# PWR.net
KiCad netlist of a schematic drawn in Altium Designer
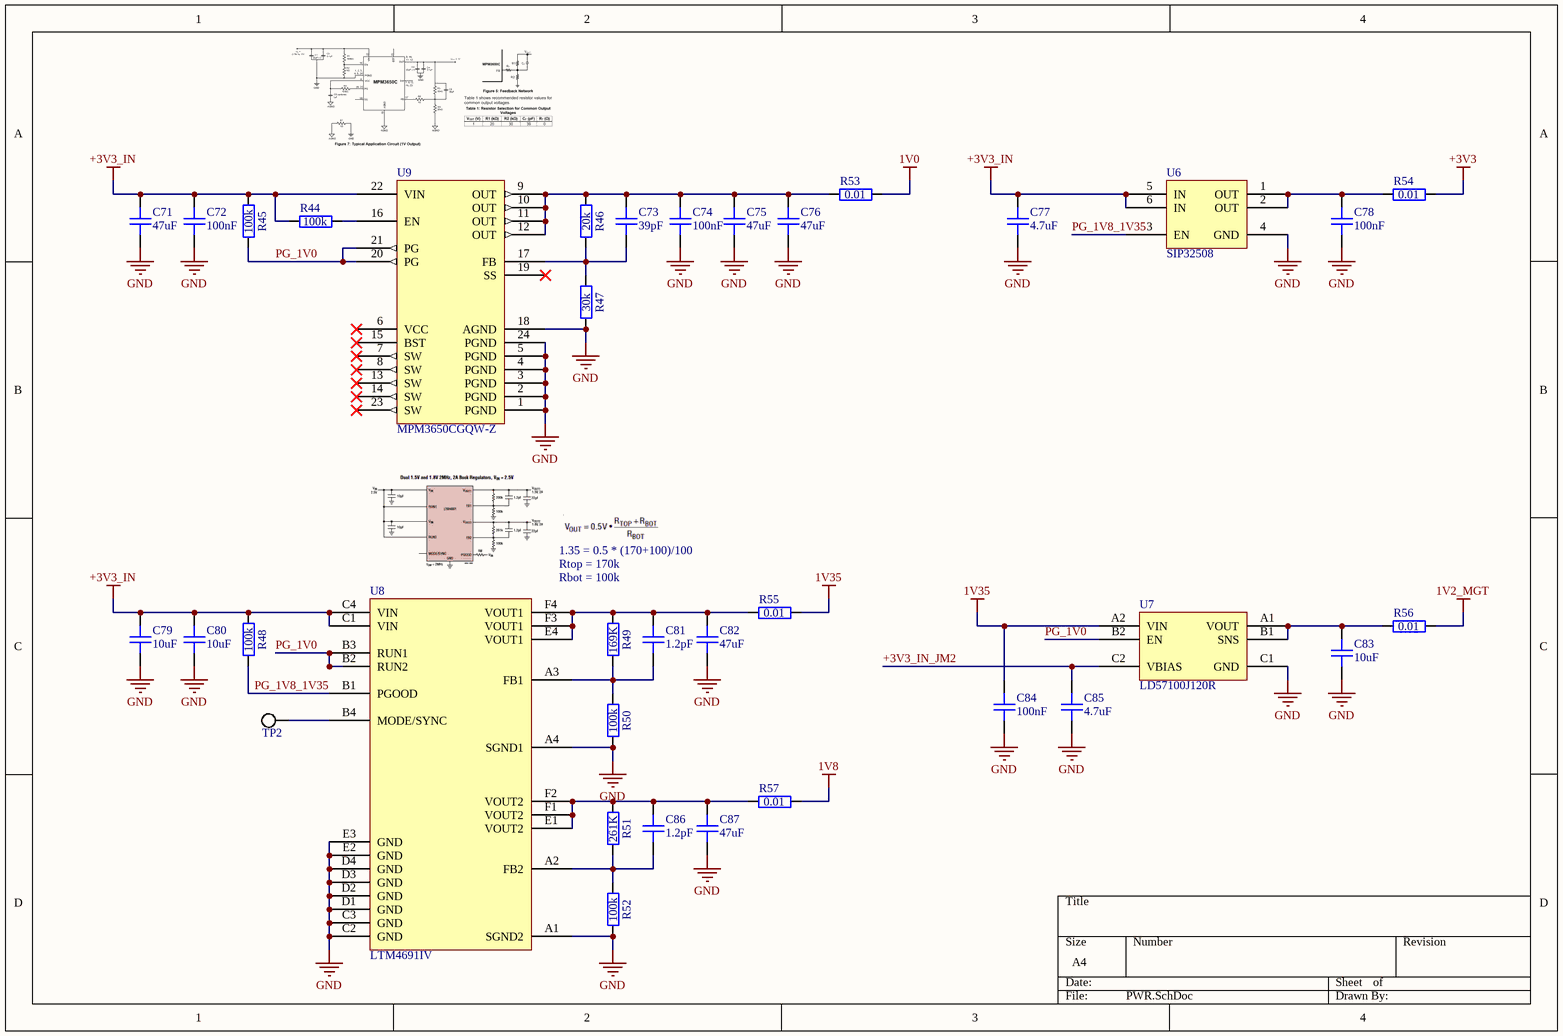
[diagram p0: PWR.SchDoc]

(export (version "E")
  (design (tool "Eeschema 10.0.6"))
  (components
    (comp (ref "C71")
      (value "47uF")
      (footprint "GEN_C_0805")
      (libsource (lib "DSO") (part "CAP 47uF 6.3V X5R 0805"))
    )
    (comp (ref "C72")
      (value "100nF")
      (footprint "GEN_C_0402")
      (libsource (lib "DSO") (part "CAP 100nF 16V X7R 0402"))
    )
    (comp (ref "C73")
      (value "39pF")
      (footprint "GEN_C_0402")
      (libsource (lib "DSO") (part "CAP 39pF 50V C0G 0402"))
    )
    (comp (ref "C74")
      (value "100nF")
      (footprint "GEN_C_0402")
      (libsource (lib "DSO") (part "CAP 100nF 16V X7R 0402"))
    )
    (comp (ref "C75")
      (value "47uF")
      (footprint "GEN_C_0805")
      (libsource (lib "DSO") (part "CAP 47uF 6.3V X5R 0805"))
    )
    (comp (ref "C76")
      (value "47uF")
      (footprint "GEN_C_0805")
      (libsource (lib "DSO") (part "CAP 47uF 6.3V X5R 0805"))
    )
    (comp (ref "C77")
      (value "4.7uF")
      (footprint "GEN_C_0402")
      (libsource (lib "DSO") (part "CAP 4.7uF 6.3V X5R 0402"))
    )
    (comp (ref "C78")
      (value "100nF")
      (footprint "GEN_C_0402")
      (libsource (lib "DSO") (part "CAP 100nF 16V X7R 0402"))
    )
    (comp (ref "C79")
      (value "10uF")
      (footprint "GEN_C_0603")
      (libsource (lib "DSO") (part "CAP 10uF 10V X5R 0603"))
    )
    (comp (ref "C80")
      (value "10uF")
      (footprint "GEN_C_0603")
      (libsource (lib "DSO") (part "CAP 10uF 10V X5R 0603"))
    )
    (comp (ref "C81")
      (value "1.2pF")
      (footprint "GEN_C_0402")
      (libsource (lib "DSO") (part "CAP 1.2pF 50V C0G 0402"))
    )
    (comp (ref "C82")
      (value "47uF")
      (footprint "GEN_C_0805")
      (libsource (lib "DSO") (part "CAP 47uF 6.3V X5R 0805"))
    )
    (comp (ref "C83")
      (value "10uF")
      (footprint "GEN_C_0603")
      (libsource (lib "DSO") (part "CAP 10uF 10V X5R 0603"))
    )
    (comp (ref "C84")
      (value "100nF")
      (footprint "GEN_C_0402")
      (libsource (lib "DSO") (part "CAP 100nF 16V X7R 0402"))
    )
    (comp (ref "C85")
      (value "4.7uF")
      (footprint "GEN_C_0402")
      (libsource (lib "DSO") (part "CAP 4.7uF 6.3V X5R 0402"))
    )
    (comp (ref "C86")
      (value "1.2pF")
      (footprint "GEN_C_0402")
      (libsource (lib "DSO") (part "CAP 1.2pF 50V C0G 0402"))
    )
    (comp (ref "C87")
      (value "47uF")
      (footprint "GEN_C_0805")
      (libsource (lib "DSO") (part "CAP 47uF 6.3V X5R 0805"))
    )
    (comp (ref "R44")
      (value "100k")
      (footprint "GEN_R_0402")
      (fields (field (name "TOLERANCE") "1%"))
      (libsource (lib "") (part "RES 100K OHM 1% 1/10W 0402_1"))
    )
    (comp (ref "R45")
      (value "100k")
      (footprint "GEN_R_0402")
      (fields (field (name "TOLERANCE") "1%"))
      (libsource (lib "DSO") (part "RES 100K OHM 1% 1/10W 0402"))
    )
    (comp (ref "R46")
      (value "20k")
      (footprint "GEN_R_0402")
      (fields (field (name "TOLERANCE") "1%"))
      (libsource (lib "DSO") (part "RES 20K OHM 1% 1/16W 0402"))
    )
    (comp (ref "R47")
      (value "30k")
      (footprint "GEN_R_0402")
      (fields (field (name "TOLERANCE") "1%"))
      (libsource (lib "DSO") (part "RES 30K OHM 1% 1/16W 0402"))
    )
    (comp (ref "R48")
      (value "100k")
      (footprint "GEN_R_0402")
      (fields (field (name "TOLERANCE") "1%"))
      (libsource (lib "DSO") (part "RES 100K OHM 1% 1/10W 0402"))
    )
    (comp (ref "R49")
      (value "169K")
      (footprint "GEN_R_0402")
      (fields (field (name "TOLERANCE") "1%"))
      (libsource (lib "DSO") (part "RES 169K OHM 1% 1/16W 0402"))
    )
    (comp (ref "R50")
      (value "100k")
      (footprint "GEN_R_0402")
      (fields (field (name "TOLERANCE") "1%"))
      (libsource (lib "DSO") (part "RES 100K OHM 1% 1/10W 0402"))
    )
    (comp (ref "R51")
      (value "261K")
      (footprint "GEN_R_0402")
      (fields (field (name "TOLERANCE") "1%"))
      (libsource (lib "DSO") (part "RES 261K OHM 1% 1/16W 0402"))
    )
    (comp (ref "R52")
      (value "100k")
      (footprint "GEN_R_0402")
      (fields (field (name "TOLERANCE") "1%"))
      (libsource (lib "DSO") (part "RES 100K OHM 1% 1/10W 0402"))
    )
    (comp (ref "R53")
      (value "0.01")
      (footprint "GEN_R_0603")
      (fields (field (name "TOLERANCE") "1%"))
      (libsource (lib "DSO") (part "RES 0.01 OHM 1% 1/4W 0603"))
    )
    (comp (ref "R54")
      (value "0.01")
      (footprint "GEN_R_0603")
      (fields (field (name "TOLERANCE") "1%"))
      (libsource (lib "DSO") (part "RES 0.01 OHM 1% 1/4W 0603"))
    )
    (comp (ref "R55")
      (value "0.01")
      (footprint "GEN_R_0603")
      (fields (field (name "TOLERANCE") "1%"))
      (libsource (lib "DSO") (part "RES 0.01 OHM 1% 1/4W 0603"))
    )
    (comp (ref "R56")
      (value "0.01")
      (footprint "GEN_R_0603")
      (fields (field (name "TOLERANCE") "1%"))
      (libsource (lib "DSO") (part "RES 0.01 OHM 1% 1/4W 0603"))
    )
    (comp (ref "R57")
      (value "0.01")
      (footprint "GEN_R_0603")
      (fields (field (name "TOLERANCE") "1%"))
      (libsource (lib "DSO") (part "RES 0.01 OHM 1% 1/4W 0603"))
    )
    (comp (ref "TP2") (value "PCB") (footprint "GEN_TP_PCB") (libsource (lib "DSO") (part "TP PCB 1mm")))
    (comp (ref "U6")
      (value "SIP32508")
      (footprint "VISH_TSOT6")
      (libsource (lib "DSO") (part "IC SWITCH LOAD SIP32508"))
    )
    (comp (ref "U7")
      (value "LD57100J120R")
      (footprint "ST_FlipChip6")
      (libsource (lib "DSO") (part "IC LDO LD57100J120R"))
    )
    (comp (ref "U8")
      (value "LTM4691IV")
      (footprint "AD_LGA24")
      (libsource (lib "DSO") (part "IC BUCK LTM4691IV"))
    )
    (comp (ref "U9")
      (value "MPM3650CGQW-Z")
      (footprint "MPS_MPM3650")
      (libsource (lib "DSO") (part "IC BUCK MPM3650CGQW-Z"))
    )
  )
  (nets
    (net (code "1") (name "+3V3") (class "Default")
      (node (ref "R54") (pin "2") (pinfunction "2_2") (pintype "passive"))
    )
    (net (code "2") (name "+3V3_IN") (class "Default")
      (node (ref "C71") (pin "2") (pinfunction "2_2") (pintype "passive"))
      (node (ref "C72") (pin "2") (pinfunction "2_2") (pintype "passive"))
      (node (ref "C77") (pin "2") (pinfunction "2_2") (pintype "passive"))
      (node (ref "C79") (pin "2") (pinfunction "2_2") (pintype "passive"))
      (node (ref "C80") (pin "2") (pinfunction "2_2") (pintype "passive"))
      (node (ref "R44") (pin "1") (pinfunction "1_1") (pintype "passive"))
      (node (ref "R45") (pin "2") (pinfunction "2_2") (pintype "passive"))
      (node (ref "R48") (pin "2") (pinfunction "2_2") (pintype "passive"))
      (node (ref "U6") (pin "5") (pinfunction "IN_5") (pintype "passive"))
      (node (ref "U6") (pin "6") (pinfunction "IN_6") (pintype "passive"))
      (node (ref "U8") (pin "C1") (pinfunction "VIN_C1") (pintype "passive"))
      (node (ref "U8") (pin "C4") (pinfunction "VIN_C4") (pintype "passive"))
      (node (ref "U9") (pin "22") (pinfunction "VIN_22") (pintype "power_in"))
    )
    (net (code "3") (name "/+3V3_IN_JM2") (class "Default")
      (node (ref "C85") (pin "2") (pinfunction "2_2") (pintype "passive"))
      (node (ref "U7") (pin "C2") (pinfunction "VBIAS_C2") (pintype "passive"))
    )
    (net (code "4") (name "/PG_1V0") (class "Default")
      (node (ref "R45") (pin "1") (pinfunction "1_1") (pintype "passive"))
      (node (ref "U7") (pin "B2") (pinfunction "EN_B2") (pintype "passive"))
      (node (ref "U8") (pin "B2") (pinfunction "RUN2_B2") (pintype "passive"))
      (node (ref "U8") (pin "B3") (pinfunction "RUN1_B3") (pintype "passive"))
      (node (ref "U9") (pin "20") (pinfunction "PG_20") (pintype "output"))
      (node (ref "U9") (pin "21") (pinfunction "PG_21") (pintype "output"))
    )
    (net (code "5") (name "/PG_1V8_1V35") (class "Default")
      (node (ref "R48") (pin "1") (pinfunction "1_1") (pintype "passive"))
      (node (ref "U6") (pin "3") (pinfunction "EN_3") (pintype "passive"))
      (node (ref "U8") (pin "B1") (pinfunction "PGOOD_B1") (pintype "passive"))
    )
    (net (code "6") (name "1V0") (class "Default")
      (node (ref "R53") (pin "2") (pinfunction "2_2") (pintype "passive"))
    )
    (net (code "7") (name "1V2_MGT") (class "Default")
      (node (ref "R56") (pin "2") (pinfunction "2_2") (pintype "passive"))
    )
    (net (code "8") (name "1V8") (class "Default")
      (node (ref "R57") (pin "2") (pinfunction "2_2") (pintype "passive"))
    )
    (net (code "9") (name "1V35") (class "Default")
      (node (ref "C84") (pin "2") (pinfunction "2_2") (pintype "passive"))
      (node (ref "R55") (pin "2") (pinfunction "2_2") (pintype "passive"))
      (node (ref "U7") (pin "A2") (pinfunction "VIN_A2") (pintype "passive"))
    )
    (net (code "10") (name "GND") (class "Default")
      (node (ref "C71") (pin "1") (pinfunction "1_1") (pintype "passive"))
      (node (ref "C72") (pin "1") (pinfunction "1_1") (pintype "passive"))
      (node (ref "C74") (pin "1") (pinfunction "1_1") (pintype "passive"))
      (node (ref "C75") (pin "1") (pinfunction "1_1") (pintype "passive"))
      (node (ref "C76") (pin "1") (pinfunction "1_1") (pintype "passive"))
      (node (ref "C77") (pin "1") (pinfunction "1_1") (pintype "passive"))
      (node (ref "C78") (pin "1") (pinfunction "1_1") (pintype "passive"))
      (node (ref "C79") (pin "1") (pinfunction "1_1") (pintype "passive"))
      (node (ref "C80") (pin "1") (pinfunction "1_1") (pintype "passive"))
      (node (ref "C82") (pin "1") (pinfunction "1_1") (pintype "passive"))
      (node (ref "C83") (pin "1") (pinfunction "1_1") (pintype "passive"))
      (node (ref "C84") (pin "1") (pinfunction "1_1") (pintype "passive"))
      (node (ref "C85") (pin "1") (pinfunction "1_1") (pintype "passive"))
      (node (ref "C87") (pin "1") (pinfunction "1_1") (pintype "passive"))
      (node (ref "R47") (pin "1") (pinfunction "1_1") (pintype "passive"))
      (node (ref "R50") (pin "1") (pinfunction "1_1") (pintype "passive"))
      (node (ref "R52") (pin "1") (pinfunction "1_1") (pintype "passive"))
      (node (ref "U6") (pin "4") (pinfunction "GND_4") (pintype "passive"))
      (node (ref "U7") (pin "C1") (pinfunction "GND_C1") (pintype "passive"))
      (node (ref "U8") (pin "A1") (pinfunction "SGND2_A1") (pintype "passive"))
      (node (ref "U8") (pin "A4") (pinfunction "SGND1_A4") (pintype "passive"))
      (node (ref "U8") (pin "C2") (pinfunction "GND_C2") (pintype "passive"))
      (node (ref "U8") (pin "C3") (pinfunction "GND_C3") (pintype "passive"))
      (node (ref "U8") (pin "D1") (pinfunction "GND_D1") (pintype "passive"))
      (node (ref "U8") (pin "D2") (pinfunction "GND_D2") (pintype "passive"))
      (node (ref "U8") (pin "D3") (pinfunction "GND_D3") (pintype "passive"))
      (node (ref "U8") (pin "D4") (pinfunction "GND_D4") (pintype "passive"))
      (node (ref "U8") (pin "E2") (pinfunction "GND_E2") (pintype "passive"))
      (node (ref "U8") (pin "E3") (pinfunction "GND_E3") (pintype "passive"))
      (node (ref "U9") (pin "1") (pinfunction "PGND_1") (pintype "passive"))
      (node (ref "U9") (pin "18") (pinfunction "AGND_18") (pintype "passive"))
      (node (ref "U9") (pin "2") (pinfunction "PGND_2") (pintype "passive"))
      (node (ref "U9") (pin "24") (pinfunction "PGND_24") (pintype "passive"))
      (node (ref "U9") (pin "3") (pinfunction "PGND_3") (pintype "passive"))
      (node (ref "U9") (pin "4") (pinfunction "PGND_4") (pintype "passive"))
      (node (ref "U9") (pin "5") (pinfunction "PGND_5") (pintype "passive"))
    )
    (net (code "11") (name "Net-(C73-Pad2)") (class "Default")
      (node (ref "C73") (pin "2") (pinfunction "2_2") (pintype "passive"))
      (node (ref "C74") (pin "2") (pinfunction "2_2") (pintype "passive"))
      (node (ref "C75") (pin "2") (pinfunction "2_2") (pintype "passive"))
      (node (ref "C76") (pin "2") (pinfunction "2_2") (pintype "passive"))
      (node (ref "R46") (pin "2") (pinfunction "2_2") (pintype "passive"))
      (node (ref "R53") (pin "1") (pinfunction "1_1") (pintype "passive"))
      (node (ref "U9") (pin "10") (pinfunction "OUT_10") (pintype "output"))
      (node (ref "U9") (pin "11") (pinfunction "OUT_11") (pintype "output"))
      (node (ref "U9") (pin "12") (pinfunction "OUT_12") (pintype "output"))
      (node (ref "U9") (pin "9") (pinfunction "OUT_9") (pintype "output"))
    )
    (net (code "12") (name "Net-(C78-Pad2)") (class "Default")
      (node (ref "C78") (pin "2") (pinfunction "2_2") (pintype "passive"))
      (node (ref "R54") (pin "1") (pinfunction "1_1") (pintype "passive"))
      (node (ref "U6") (pin "1") (pinfunction "OUT_1") (pintype "passive"))
      (node (ref "U6") (pin "2") (pinfunction "OUT_2") (pintype "passive"))
    )
    (net (code "13") (name "Net-(C81-Pad2)") (class "Default")
      (node (ref "C81") (pin "2") (pinfunction "2_2") (pintype "passive"))
      (node (ref "C82") (pin "2") (pinfunction "2_2") (pintype "passive"))
      (node (ref "R49") (pin "2") (pinfunction "2_2") (pintype "passive"))
      (node (ref "R55") (pin "1") (pinfunction "1_1") (pintype "passive"))
      (node (ref "U8") (pin "E4") (pinfunction "VOUT1_E4") (pintype "passive"))
      (node (ref "U8") (pin "F3") (pinfunction "VOUT1_F3") (pintype "passive"))
      (node (ref "U8") (pin "F4") (pinfunction "VOUT1_F4") (pintype "passive"))
    )
    (net (code "14") (name "Net-(C86-Pad2)") (class "Default")
      (node (ref "C86") (pin "2") (pinfunction "2_2") (pintype "passive"))
      (node (ref "C87") (pin "2") (pinfunction "2_2") (pintype "passive"))
      (node (ref "R51") (pin "2") (pinfunction "2_2") (pintype "passive"))
      (node (ref "R57") (pin "1") (pinfunction "1_1") (pintype "passive"))
      (node (ref "U8") (pin "E1") (pinfunction "VOUT2_E1") (pintype "passive"))
      (node (ref "U8") (pin "F1") (pinfunction "VOUT2_F1") (pintype "passive"))
      (node (ref "U8") (pin "F2") (pinfunction "VOUT2_F2") (pintype "passive"))
    )
    (net (code "15") (name "Net-(U7-SNS)") (class "Default")
      (node (ref "C83") (pin "2") (pinfunction "2_2") (pintype "passive"))
      (node (ref "R56") (pin "1") (pinfunction "1_1") (pintype "passive"))
      (node (ref "U7") (pin "A1") (pinfunction "VOUT_A1") (pintype "passive"))
      (node (ref "U7") (pin "B1") (pinfunction "SNS_B1") (pintype "passive"))
    )
    (net (code "16") (name "Net-(U8-FB1)") (class "Default")
      (node (ref "C81") (pin "1") (pinfunction "1_1") (pintype "passive"))
      (node (ref "R49") (pin "1") (pinfunction "1_1") (pintype "passive"))
      (node (ref "R50") (pin "2") (pinfunction "2_2") (pintype "passive"))
      (node (ref "U8") (pin "A3") (pinfunction "FB1_A3") (pintype "passive"))
    )
    (net (code "17") (name "Net-(U8-FB2)") (class "Default")
      (node (ref "C86") (pin "1") (pinfunction "1_1") (pintype "passive"))
      (node (ref "R51") (pin "1") (pinfunction "1_1") (pintype "passive"))
      (node (ref "R52") (pin "2") (pinfunction "2_2") (pintype "passive"))
      (node (ref "U8") (pin "A2") (pinfunction "FB2_A2") (pintype "passive"))
    )
    (net (code "18") (name "Net-(U8-MODE{slash}SYNC)") (class "Default")
      (node (ref "TP2") (pin "1") (pinfunction "1_1") (pintype "passive"))
      (node (ref "U8") (pin "B4") (pinfunction "MODE/SYNC_B4") (pintype "passive"))
    )
    (net (code "19") (name "Net-(U9-EN)") (class "Default")
      (node (ref "R44") (pin "2") (pinfunction "2_2") (pintype "passive"))
      (node (ref "U9") (pin "16") (pinfunction "EN_16") (pintype "passive"))
    )
    (net (code "20") (name "Net-(U9-FB)") (class "Default")
      (node (ref "C73") (pin "1") (pinfunction "1_1") (pintype "passive"))
      (node (ref "R46") (pin "1") (pinfunction "1_1") (pintype "passive"))
      (node (ref "R47") (pin "2") (pinfunction "2_2") (pintype "passive"))
      (node (ref "U9") (pin "17") (pinfunction "FB_17") (pintype "passive"))
    )
    (net (code "21") (name "unconnected-(U9-BST-Pad15)") (class "Default")
      (node (ref "U9") (pin "15") (pinfunction "BST_15") (pintype "passive+no_connect"))
    )
    (net (code "22") (name "unconnected-(U9-SS-Pad19)") (class "Default")
      (node (ref "U9") (pin "19") (pinfunction "SS_19") (pintype "passive+no_connect"))
    )
    (net (code "23") (name "unconnected-(U9-SW-Pad7)") (class "Default")
      (node (ref "U9") (pin "7") (pinfunction "SW_7") (pintype "output+no_connect"))
    )
    (net (code "24") (name "unconnected-(U9-SW-Pad8)") (class "Default")
      (node (ref "U9") (pin "8") (pinfunction "SW_8") (pintype "output+no_connect"))
    )
    (net (code "25") (name "unconnected-(U9-SW-Pad13)") (class "Default")
      (node (ref "U9") (pin "13") (pinfunction "SW_13") (pintype "output+no_connect"))
    )
    (net (code "26") (name "unconnected-(U9-SW-Pad14)") (class "Default")
      (node (ref "U9") (pin "14") (pinfunction "SW_14") (pintype "output+no_connect"))
    )
    (net (code "27") (name "unconnected-(U9-SW-Pad23)") (class "Default")
      (node (ref "U9") (pin "23") (pinfunction "SW_23") (pintype "output+no_connect"))
    )
    (net (code "28") (name "unconnected-(U9-VCC-Pad6)") (class "Default")
      (node (ref "U9") (pin "6") (pinfunction "VCC_6") (pintype "power_in+no_connect"))
    )
  )
)
